# GatewayNode.net
KiCad netlist of a schematic drawn in EAGLE
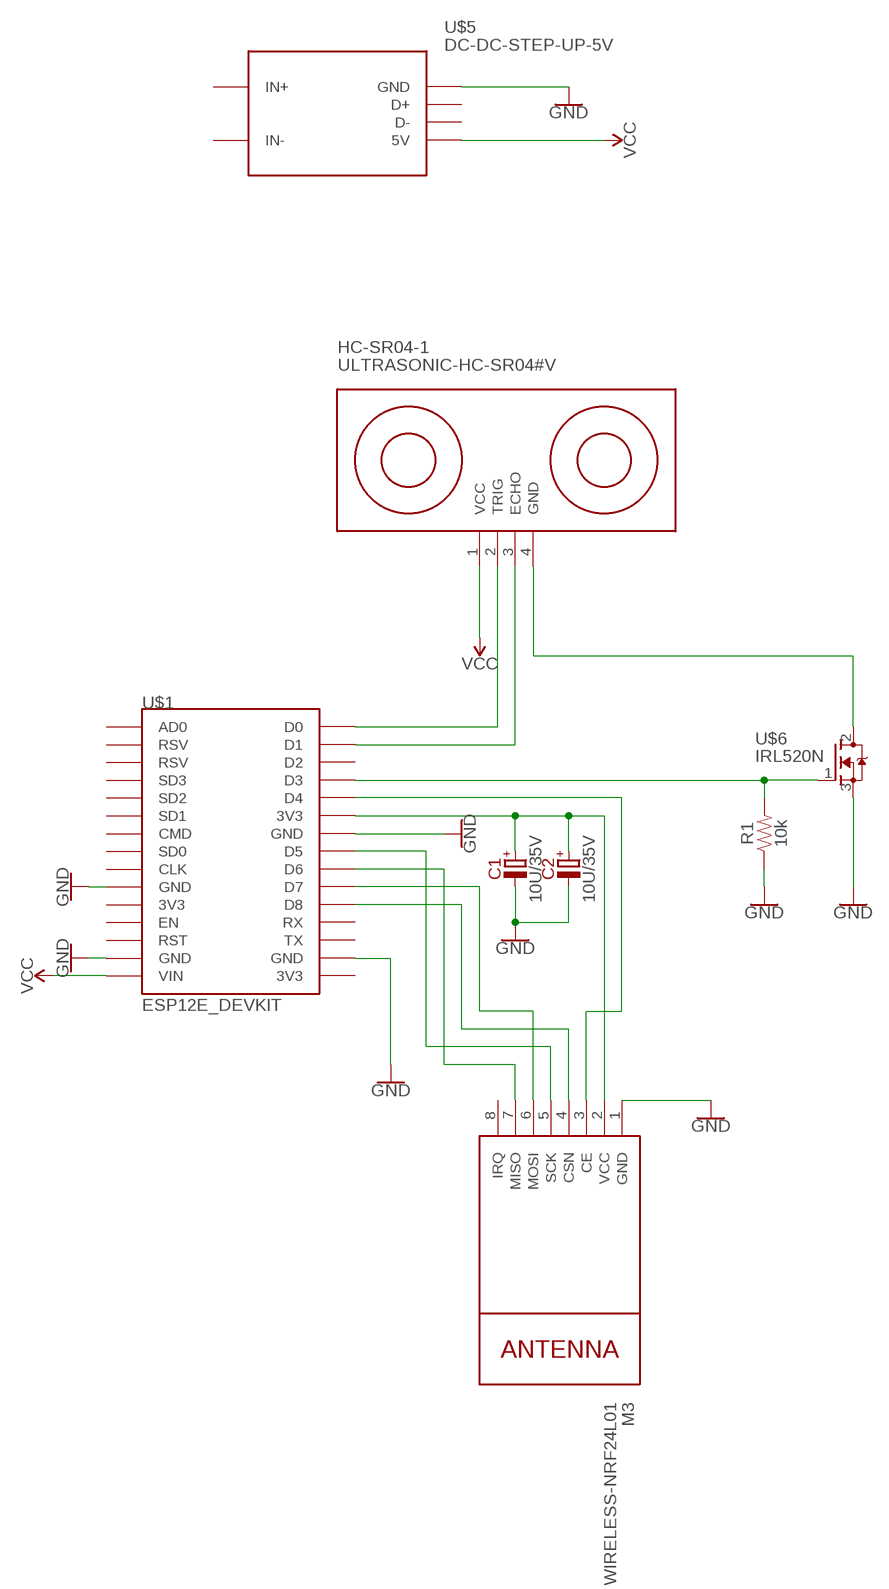
[diagram p0: schematic, sheet 1]

(export (version "E")
  (design (tool "Eeschema 10.0.6"))
  (components
    (comp (ref "C1")
      (value "10U/35V")
      (footprint "eagle-import:E2-5")
      (libsource (lib "eagle-import") (part "?10U/35V"))
    )
    (comp (ref "C2")
      (value "10U/35V")
      (footprint "eagle-import:E2-5")
      (libsource (lib "eagle-import") (part "?10U/35V"))
    )
    (comp (ref "HC-SR04-1")
      (value "ULTRASONIC-HC-SR04#V")
      (footprint "eagle-import:ULTRASONIC-HC-SR04#V")
      (libsource (lib "eagle-import") (part "ULTRASONIC-HC-SR04#V"))
    )
    (comp (ref "M3")
      (value "WIRELESS-NRF24L01")
      (footprint "eagle-import:WIRELESS-NRF24L01")
      (libsource (lib "eagle-import") (part "WIRELESS-NRF24L01"))
    )
    (comp (ref "R1")
      (value "10k")
      (footprint "eagle-import:AXIAL-0.3-KIT")
      (libsource (lib "eagle-import") (part "10KOHM-HORIZ_KIT-1/4W-1%"))
    )
    (comp (ref "U$1")
      (value "ESP12E_DEVKIT")
      (footprint "eagle-import:ESP12E_DEVKIT")
      (libsource (lib "eagle-import") (part "ESP12E_DEVKIT"))
    )
    (comp (ref "U$5")
      (value "DC-DC-STEP-UP-5V")
      (footprint "eagle-import:DC-DC-STEP-UP-5V")
      (libsource (lib "eagle-import") (part "DC-DC-STEP-UP-5V"))
    )
    (comp (ref "U$6")
      (value "IRL520N")
      (footprint "eagle-import:TO220-VERT")
      (fields (field (name "MF") "International Rectifier"))
      (libsource (lib "eagle-import") (part "IRL520N"))
    )
  )
  (nets
    (net (code "1") (name "/IN+") (class "Default")
      (node (ref "U$5") (pin "IN+") (pinfunction "IN+_IN+") (pintype "power_in"))
    )
    (net (code "2") (name "/IN-") (class "Default")
      (node (ref "U$5") (pin "IN-") (pinfunction "IN-_IN-") (pintype "power_in"))
    )
    (net (code "3") (name "GND") (class "Default")
      (node (ref "C1") (pin "-") (pinfunction "-_-") (pintype "passive"))
      (node (ref "C2") (pin "-") (pinfunction "-_-") (pintype "passive"))
      (node (ref "M3") (pin "1") (pinfunction "GND_1") (pintype "power_in"))
      (node (ref "R1") (pin "P$1") (pinfunction "1_P$1") (pintype "passive"))
      (node (ref "U$1") (pin "GND@0") (pinfunction "GND_GND@0") (pintype "bidirectional"))
      (node (ref "U$1") (pin "GND@1") (pinfunction "GND_GND@1") (pintype "bidirectional"))
      (node (ref "U$1") (pin "GND@2") (pinfunction "GND_GND@2") (pintype "bidirectional"))
      (node (ref "U$1") (pin "GND@3") (pinfunction "GND_GND@3") (pintype "bidirectional"))
      (node (ref "U$5") (pin "GND") (pinfunction "GND_GND") (pintype "bidirectional"))
      (node (ref "U$6") (pin "3") (pinfunction "S_3") (pintype "power_in"))
    )
    (net (code "4") (name "Net-(HC-SR04-1-ECHO)") (class "Default")
      (node (ref "HC-SR04-1") (pin "3") (pinfunction "ECHO_3") (pintype "output"))
      (node (ref "U$1") (pin "D1") (pinfunction "D1_D1") (pintype "bidirectional"))
    )
    (net (code "5") (name "Net-(HC-SR04-1-GND)") (class "Default")
      (node (ref "HC-SR04-1") (pin "4") (pinfunction "GND_4") (pintype "power_in"))
      (node (ref "U$6") (pin "2") (pinfunction "D_2") (pintype "power_in"))
    )
    (net (code "6") (name "Net-(HC-SR04-1-TRIG)") (class "Default")
      (node (ref "HC-SR04-1") (pin "2") (pinfunction "TRIG_2") (pintype "input"))
      (node (ref "U$1") (pin "D0") (pinfunction "D0_D0") (pintype "bidirectional"))
    )
    (net (code "7") (name "Net-(M3-CE)") (class "Default")
      (node (ref "M3") (pin "3") (pinfunction "CE_3") (pintype "bidirectional"))
      (node (ref "U$1") (pin "D4") (pinfunction "D4_D4") (pintype "bidirectional"))
    )
    (net (code "8") (name "Net-(M3-CSN)") (class "Default")
      (node (ref "M3") (pin "4") (pinfunction "CSN_4") (pintype "bidirectional"))
      (node (ref "U$1") (pin "D8") (pinfunction "D8_D8") (pintype "bidirectional"))
    )
    (net (code "9") (name "Net-(M3-MISO)") (class "Default")
      (node (ref "M3") (pin "7") (pinfunction "MISO_7") (pintype "bidirectional"))
      (node (ref "U$1") (pin "D6") (pinfunction "D6_D6") (pintype "bidirectional"))
    )
    (net (code "10") (name "Net-(M3-MOSI)") (class "Default")
      (node (ref "M3") (pin "6") (pinfunction "MOSI_6") (pintype "bidirectional"))
      (node (ref "U$1") (pin "D7") (pinfunction "D7_D7") (pintype "bidirectional"))
    )
    (net (code "11") (name "Net-(M3-SCK)") (class "Default")
      (node (ref "M3") (pin "5") (pinfunction "SCK_5") (pintype "bidirectional"))
      (node (ref "U$1") (pin "D5") (pinfunction "D5_D5") (pintype "bidirectional"))
    )
    (net (code "12") (name "Net-(M3-VCC)") (class "Default")
      (node (ref "C1") (pin "+") (pinfunction "+_+") (pintype "passive"))
      (node (ref "C2") (pin "+") (pinfunction "+_+") (pintype "passive"))
      (node (ref "M3") (pin "2") (pinfunction "VCC_2") (pintype "power_in"))
      (node (ref "U$1") (pin "3V3@1") (pinfunction "3V3_3V3@1") (pintype "bidirectional"))
    )
    (net (code "13") (name "Net-(R1-2)") (class "Default")
      (node (ref "R1") (pin "P$2") (pinfunction "2_P$2") (pintype "passive"))
      (node (ref "U$1") (pin "D3") (pinfunction "D3_D3") (pintype "bidirectional"))
      (node (ref "U$6") (pin "1") (pinfunction "G_1") (pintype "power_in"))
    )
    (net (code "14") (name "VCC") (class "Default")
      (node (ref "HC-SR04-1") (pin "1") (pinfunction "VCC_1") (pintype "power_in"))
      (node (ref "U$1") (pin "VIN") (pinfunction "VIN_VIN") (pintype "bidirectional"))
      (node (ref "U$5") (pin "5V") (pinfunction "5V_5V") (pintype "bidirectional"))
    )
    (net (code "15") (name "unconnected-(M3-IRQ-Pad8)") (class "Default")
      (node (ref "M3") (pin "8") (pinfunction "IRQ_8") (pintype "bidirectional"))
    )
    (net (code "16") (name "unconnected-(U$1-3V3-Pad3V3@0)") (class "Default")
      (node (ref "U$1") (pin "3V3@0") (pinfunction "3V3_3V3@0") (pintype "bidirectional"))
    )
    (net (code "17") (name "unconnected-(U$1-3V3-Pad3V3@2)") (class "Default")
      (node (ref "U$1") (pin "3V3@2") (pinfunction "3V3_3V3@2") (pintype "bidirectional"))
    )
    (net (code "18") (name "unconnected-(U$1-PadAD0)") (class "Default")
      (node (ref "U$1") (pin "AD0") (pinfunction "AD0_AD0") (pintype "bidirectional"))
    )
    (net (code "19") (name "unconnected-(U$1-PadCLK)") (class "Default")
      (node (ref "U$1") (pin "CLK") (pinfunction "CLK_CLK") (pintype "bidirectional"))
    )
    (net (code "20") (name "unconnected-(U$1-PadCMD)") (class "Default")
      (node (ref "U$1") (pin "CMD") (pinfunction "CMD_CMD") (pintype "bidirectional"))
    )
    (net (code "21") (name "unconnected-(U$1-PadD2)") (class "Default")
      (node (ref "U$1") (pin "D2") (pinfunction "D2_D2") (pintype "bidirectional"))
    )
    (net (code "22") (name "unconnected-(U$1-PadEN)") (class "Default")
      (node (ref "U$1") (pin "EN") (pinfunction "EN_EN") (pintype "bidirectional"))
    )
    (net (code "23") (name "unconnected-(U$1-PadRST)") (class "Default")
      (node (ref "U$1") (pin "RST") (pinfunction "RST_RST") (pintype "bidirectional"))
    )
    (net (code "24") (name "unconnected-(U$1-PadRX)") (class "Default")
      (node (ref "U$1") (pin "RX") (pinfunction "RX_RX") (pintype "bidirectional"))
    )
    (net (code "25") (name "unconnected-(U$1-PadSD0)") (class "Default")
      (node (ref "U$1") (pin "SD0") (pinfunction "SD0_SD0") (pintype "bidirectional"))
    )
    (net (code "26") (name "unconnected-(U$1-PadSD1)") (class "Default")
      (node (ref "U$1") (pin "SD1") (pinfunction "SD1_SD1") (pintype "bidirectional"))
    )
    (net (code "27") (name "unconnected-(U$1-PadSD2)") (class "Default")
      (node (ref "U$1") (pin "SD2") (pinfunction "SD2_SD2") (pintype "bidirectional"))
    )
    (net (code "28") (name "unconnected-(U$1-PadSD3)") (class "Default")
      (node (ref "U$1") (pin "SD3") (pinfunction "SD3_SD3") (pintype "bidirectional"))
    )
    (net (code "29") (name "unconnected-(U$1-PadTX)") (class "Default")
      (node (ref "U$1") (pin "TX") (pinfunction "TX_TX") (pintype "bidirectional"))
    )
    (net (code "30") (name "unconnected-(U$1-RSV-PadRSV@0)") (class "Default")
      (node (ref "U$1") (pin "RSV@0") (pinfunction "RSV_RSV@0") (pintype "bidirectional"))
    )
    (net (code "31") (name "unconnected-(U$1-RSV-PadRSV@1)") (class "Default")
      (node (ref "U$1") (pin "RSV@1") (pinfunction "RSV_RSV@1") (pintype "bidirectional"))
    )
    (net (code "32") (name "unconnected-(U$5-PadD+)") (class "Default")
      (node (ref "U$5") (pin "D+") (pinfunction "D+_D+") (pintype "bidirectional"))
    )
    (net (code "33") (name "unconnected-(U$5-PadD-)") (class "Default")
      (node (ref "U$5") (pin "D-") (pinfunction "D-_D-") (pintype "bidirectional"))
    )
  )
)
